# LoRa_test.net
KiCad netlist of a schematic drawn in EAGLE
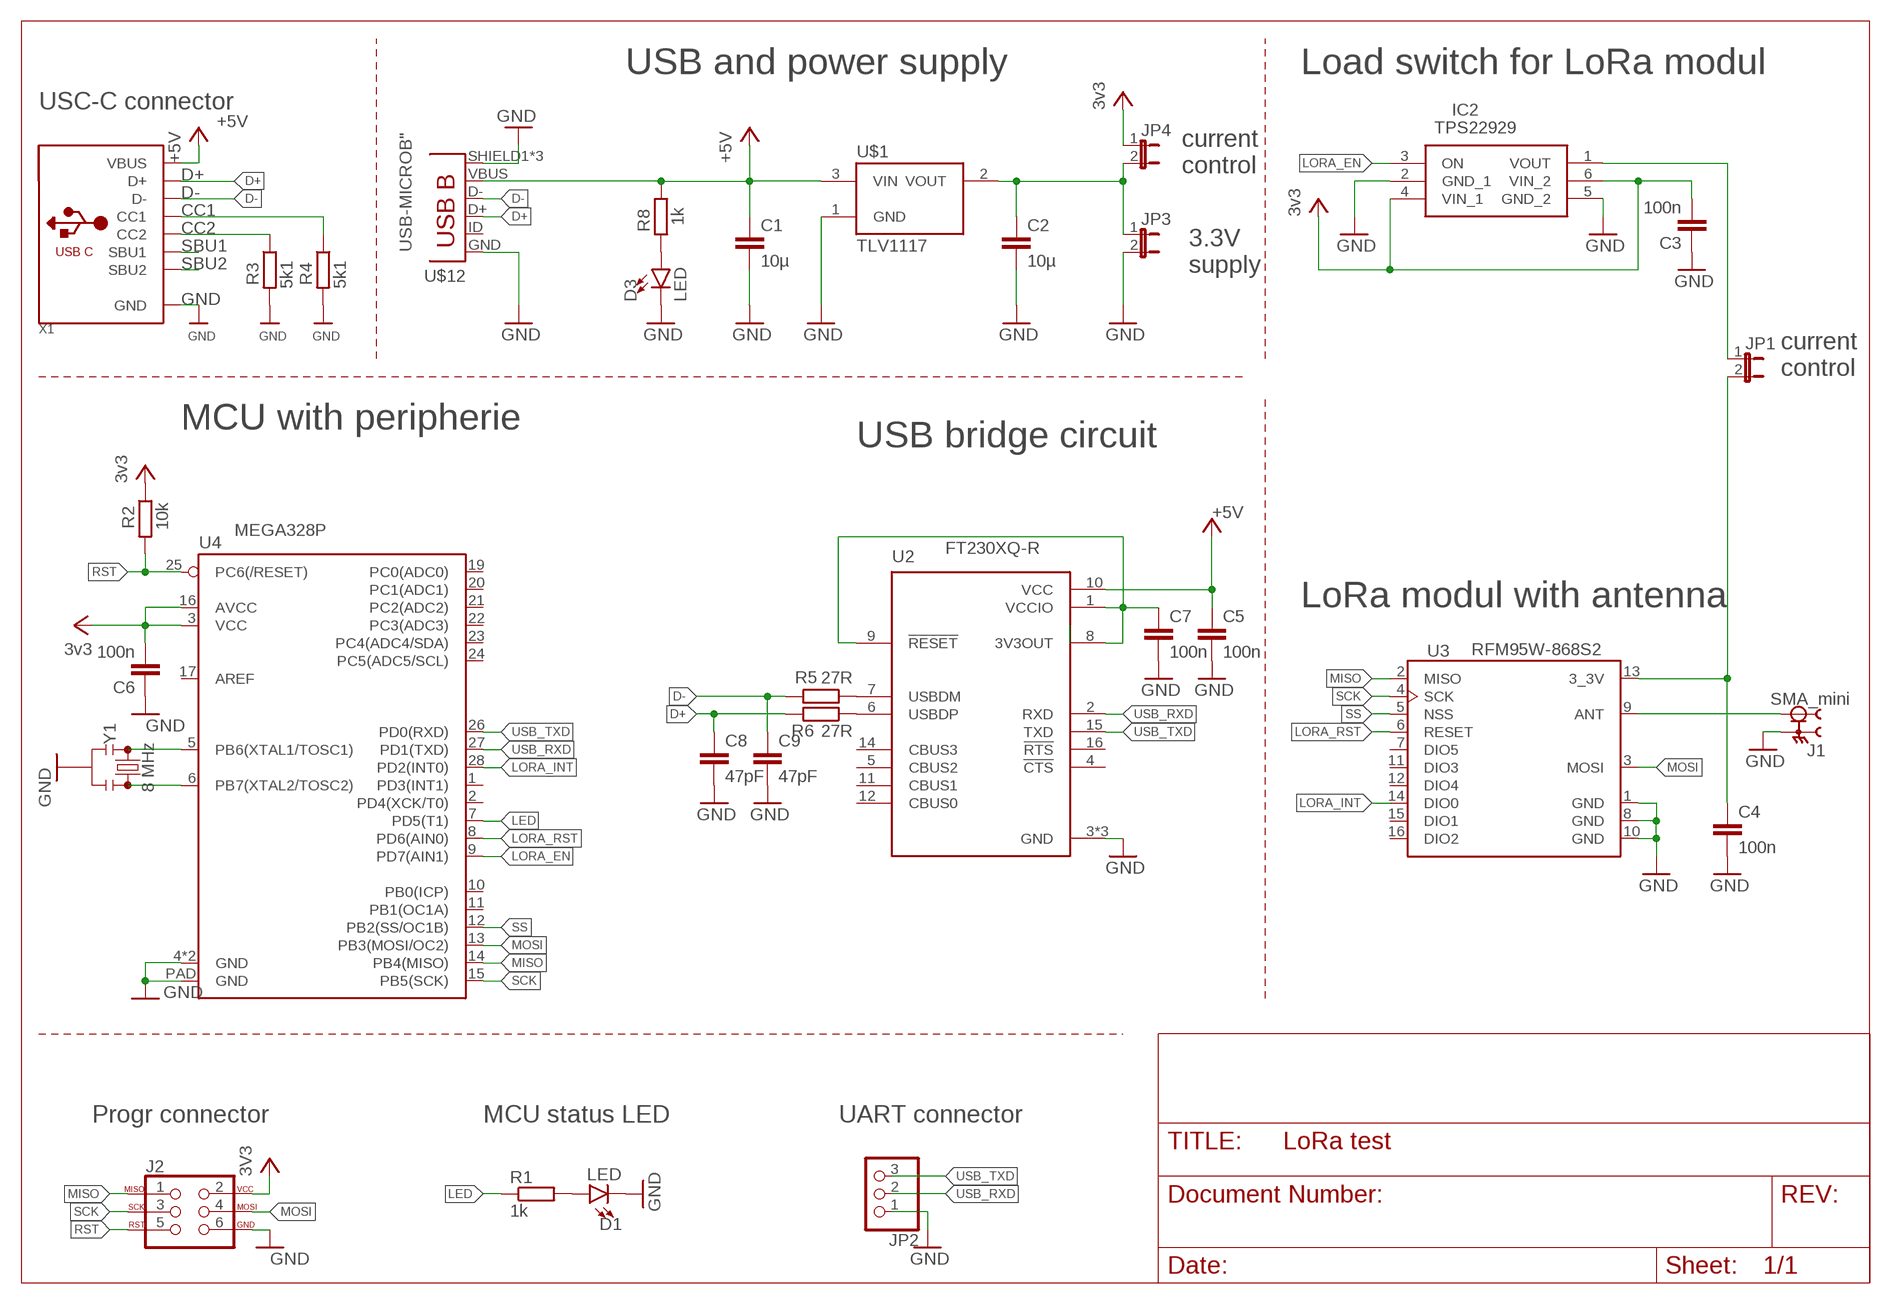
[diagram p0: schematic, sheet 1]

(export (version "E")
  (design (tool "Eeschema 10.0.6"))
  (components
    (comp (ref "C1")
      (value "10µ")
      (footprint "eagle-import:C1206K")
      (libsource (lib "eagle-import") (part "rcl_334_C-EUC1206K"))
    )
    (comp (ref "C2")
      (value "10µ")
      (footprint "eagle-import:C1206K")
      (libsource (lib "eagle-import") (part "rcl_334_C-EUC1206K"))
    )
    (comp (ref "C3")
      (value "100n")
      (footprint "eagle-import:C0603")
      (libsource (lib "eagle-import") (part "C-EUC0603"))
    )
    (comp (ref "C4")
      (value "100n")
      (footprint "eagle-import:C0603")
      (libsource (lib "eagle-import") (part "C-EUC0603"))
    )
    (comp (ref "C5")
      (value "100n")
      (footprint "eagle-import:C0603")
      (libsource (lib "eagle-import") (part "C-EUC0603"))
    )
    (comp (ref "C6")
      (value "100n")
      (footprint "eagle-import:C0603")
      (libsource (lib "eagle-import") (part "C-EUC0603"))
    )
    (comp (ref "C7")
      (value "100n")
      (footprint "eagle-import:C0603")
      (libsource (lib "eagle-import") (part "C-EUC0603"))
    )
    (comp (ref "C8")
      (value "47pF")
      (footprint "eagle-import:C0603")
      (libsource (lib "eagle-import") (part "C-EUC0603"))
    )
    (comp (ref "C9")
      (value "47pF")
      (footprint "eagle-import:C0603")
      (libsource (lib "eagle-import") (part "C-EUC0603"))
    )
    (comp (ref "D1")
      (value "LED")
      (footprint "eagle-import:LED-0603")
      (libsource (lib "eagle-import") (part "LED-RED0603-SMART"))
    )
    (comp (ref "D3")
      (value "LED")
      (footprint "eagle-import:LED-0603")
      (libsource (lib "eagle-import") (part "LED-RED0603"))
    )
    (comp (ref "IC2")
      (value "TPS22929")
      (footprint "eagle-import:SOP95P280X145-6N")
      (fields
        (field (name "ARROW_PART_NUMBER") "TPS22929DDBVR")
        (field (name "MOUSER_PART_NUMBER") "595-TPS22929DDBVR")
      )
      (libsource (lib "eagle-import") (part "TPS22929DDBVR"))
    )
    (comp (ref "J1")
      (value "SMA_mini")
      (footprint "eagle-import:LPRS_SMA_CONNECTOR")
      (fields (field (name "MF") "LPRS") (field (name "MP") "SMA CONNECTOR"))
      (libsource (lib "eagle-import") (part "SMA_CONNECTOR"))
    )
    (comp (ref "J2")
      (value "AVR_SPI_PROG_3X2NS")
      (footprint "eagle-import:2X3-NS")
      (libsource (lib "eagle-import") (part "AVR_SPI_PROG_3X2NS"))
    )
    (comp (ref "JP1")
      (value "JP1E")
      (footprint "eagle-import:JP1")
      (libsource (lib "eagle-import") (part "JP1E"))
    )
    (comp (ref "JP2")
      (value "PINHD-1X3")
      (footprint "eagle-import:1X03")
      (libsource (lib "eagle-import") (part "PINHD-1X3"))
    )
    (comp (ref "JP3")
      (value "JP1E")
      (footprint "eagle-import:JP1")
      (libsource (lib "eagle-import") (part "JP1E"))
    )
    (comp (ref "JP4")
      (value "JP1E")
      (footprint "eagle-import:JP1")
      (libsource (lib "eagle-import") (part "JP1E"))
    )
    (comp (ref "R1")
      (value "1k")
      (footprint "eagle-import:R0603")
      (libsource (lib "eagle-import") (part "R-EU_R0603"))
    )
    (comp (ref "R2")
      (value "10k")
      (footprint "eagle-import:R0603")
      (libsource (lib "eagle-import") (part "R-EU_R0603"))
    )
    (comp (ref "R3")
      (value "5k1")
      (footprint "eagle-import:R0603")
      (libsource (lib "eagle-import") (part "R-EU_R0603"))
    )
    (comp (ref "R4")
      (value "5k1")
      (footprint "eagle-import:R0603")
      (libsource (lib "eagle-import") (part "R-EU_R0603"))
    )
    (comp (ref "R5")
      (value "27R")
      (footprint "eagle-import:R0603")
      (libsource (lib "eagle-import") (part "R-EU_R0603"))
    )
    (comp (ref "R6")
      (value "27R")
      (footprint "eagle-import:R0603")
      (libsource (lib "eagle-import") (part "R-EU_R0603"))
    )
    (comp (ref "R8")
      (value "1k")
      (footprint "eagle-import:R0603")
      (libsource (lib "eagle-import") (part "R-EU_R0603"))
    )
    (comp (ref "U$1")
      (value "TLV1117")
      (footprint "eagle-import:SOT223")
      (libsource (lib "eagle-import") (part "TLV1117"))
    )
    (comp (ref "U$12")
      (value "USB-MICROB\"")
      (footprint "eagle-import:USB-B-MICRO-SMD_V03")
      (libsource (lib "eagle-import") (part "USB-MICROB{dblquote}"))
    )
    (comp (ref "U2")
      (value "FT230XQ-R")
      (footprint "eagle-import:QFN65P400X400X80-17N")
      (fields (field (name "MF") "FTDI,"))
      (libsource (lib "eagle-import") (part "FT230XQ-R"))
    )
    (comp (ref "U3")
      (value "RFM95W-868S2")
      (footprint "eagle-import:XCVR_RFM95W-868S2")
      (fields (field (name "MF") "HOPERF"))
      (libsource (lib "eagle-import") (part "RFM95W-868S2"))
    )
    (comp (ref "U4")
      (value "MEGA328P")
      (footprint "eagle-import:VQFN-28")
      (libsource (lib "eagle-import") (part "ATMEGA328P_VQFNVQFN"))
    )
    (comp (ref "X1")
      (value "USB_C")
      (footprint "eagle-import:USB_C_CUSB31-CFM2AX-01-X")
      (libsource (lib "eagle-import") (part "USB_C"))
    )
    (comp (ref "Y1")
      (value "8 MHz")
      (footprint "eagle-import:RESONATOR-SMD-3.2X1.3")
      (libsource (lib "eagle-import") (part "RESONATORSMD-3.2X1.3"))
    )
  )
  (nets
    (net (code "1") (name "+5V") (class "Default")
      (node (ref "C1") (pin "1") (pinfunction "1_1") (pintype "passive"))
      (node (ref "C5") (pin "1") (pinfunction "1_1") (pintype "passive"))
      (node (ref "R8") (pin "1") (pinfunction "1_1") (pintype "passive"))
      (node (ref "U$1") (pin "3") (pinfunction "VIN_3") (pintype "power_in"))
      (node (ref "U$12") (pin "VBUS") (pinfunction "VBUS_VBUS") (pintype "bidirectional"))
      (node (ref "U2") (pin "10") (pinfunction "VCC_10") (pintype "power_in"))
      (node (ref "X1") (pin "A4B9") (pinfunction "VBUS_A4B9") (pintype "power_in"))
      (node (ref "X1") (pin "B4A9") (pinfunction "VBUS_B4A9") (pintype "power_in"))
    )
    (net (code "2") (name "/CC1") (class "Default")
      (node (ref "R4") (pin "1") (pinfunction "1_1") (pintype "passive"))
      (node (ref "X1") (pin "A5") (pinfunction "CC1_A5") (pintype "bidirectional"))
    )
    (net (code "3") (name "/CC2") (class "Default")
      (node (ref "R3") (pin "1") (pinfunction "1_1") (pintype "passive"))
      (node (ref "X1") (pin "B5") (pinfunction "CC2_B5") (pintype "bidirectional"))
    )
    (net (code "4") (name "/SBU1") (class "Default")
      (node (ref "X1") (pin "A8") (pinfunction "SBU1_A8") (pintype "bidirectional"))
    )
    (net (code "5") (name "/SBU2") (class "Default")
      (node (ref "X1") (pin "B8") (pinfunction "SBU2_B8") (pintype "bidirectional"))
    )
    (net (code "6") (name "3V3") (class "Default")
      (node (ref "C3") (pin "2") (pinfunction "2_2") (pintype "passive"))
      (node (ref "C6") (pin "2") (pinfunction "2_2") (pintype "passive"))
      (node (ref "IC2") (pin "4") (pinfunction "VIN_1_4") (pintype "bidirectional"))
      (node (ref "IC2") (pin "6") (pinfunction "VIN_2_6") (pintype "bidirectional"))
      (node (ref "J2") (pin "2") (pinfunction "2_2") (pintype "passive"))
      (node (ref "JP4") (pin "1") (pinfunction "1_1") (pintype "passive"))
      (node (ref "R2") (pin "1") (pinfunction "1_1") (pintype "passive"))
      (node (ref "U4") (pin "16") (pinfunction "AVCC_16") (pintype "bidirectional"))
      (node (ref "U4") (pin "3") (pinfunction "VCC_3") (pintype "bidirectional"))
    )
    (net (code "7") (name "D+") (class "Default")
      (node (ref "C8") (pin "1") (pinfunction "1_1") (pintype "passive"))
      (node (ref "R6") (pin "2") (pinfunction "2_2") (pintype "passive"))
      (node (ref "U$12") (pin "D+") (pinfunction "D+_D+") (pintype "bidirectional"))
      (node (ref "X1") (pin "A6") (pinfunction "D+_A6") (pintype "bidirectional"))
      (node (ref "X1") (pin "B6") (pinfunction "D+_B6") (pintype "bidirectional"))
    )
    (net (code "8") (name "D-") (class "Default")
      (node (ref "C9") (pin "1") (pinfunction "1_1") (pintype "passive"))
      (node (ref "R5") (pin "2") (pinfunction "2_2") (pintype "passive"))
      (node (ref "U$12") (pin "D-") (pinfunction "D-_D-") (pintype "bidirectional"))
      (node (ref "X1") (pin "A7") (pinfunction "D-_A7") (pintype "bidirectional"))
      (node (ref "X1") (pin "B7") (pinfunction "D-_B7") (pintype "bidirectional"))
    )
    (net (code "9") (name "GND") (class "Default")
      (node (ref "C1") (pin "2") (pinfunction "2_2") (pintype "passive"))
      (node (ref "C2") (pin "2") (pinfunction "2_2") (pintype "passive"))
      (node (ref "C3") (pin "1") (pinfunction "1_1") (pintype "passive"))
      (node (ref "C4") (pin "2") (pinfunction "2_2") (pintype "passive"))
      (node (ref "C5") (pin "2") (pinfunction "2_2") (pintype "passive"))
      (node (ref "C6") (pin "1") (pinfunction "1_1") (pintype "passive"))
      (node (ref "C7") (pin "2") (pinfunction "2_2") (pintype "passive"))
      (node (ref "C8") (pin "2") (pinfunction "2_2") (pintype "passive"))
      (node (ref "C9") (pin "2") (pinfunction "2_2") (pintype "passive"))
      (node (ref "D1") (pin "C") (pinfunction "C_C") (pintype "passive"))
      (node (ref "D3") (pin "C") (pinfunction "C_C") (pintype "passive"))
      (node (ref "IC2") (pin "2") (pinfunction "GND_1_2") (pintype "bidirectional"))
      (node (ref "IC2") (pin "5") (pinfunction "GND_2_5") (pintype "bidirectional"))
      (node (ref "J1") (pin "G1") (pinfunction "2_G1") (pintype "passive"))
      (node (ref "J1") (pin "G2") (pinfunction "2_G2") (pintype "passive"))
      (node (ref "J1") (pin "G3") (pinfunction "2_G3") (pintype "passive"))
      (node (ref "J1") (pin "G4") (pinfunction "2_G4") (pintype "passive"))
      (node (ref "J2") (pin "6") (pinfunction "6_6") (pintype "passive"))
      (node (ref "JP2") (pin "1") (pinfunction "1_1") (pintype "passive"))
      (node (ref "JP3") (pin "2") (pinfunction "2_2") (pintype "passive"))
      (node (ref "R3") (pin "2") (pinfunction "2_2") (pintype "passive"))
      (node (ref "R4") (pin "2") (pinfunction "2_2") (pintype "passive"))
      (node (ref "U$1") (pin "1") (pinfunction "GND_1") (pintype "power_in"))
      (node (ref "U$12") (pin "GND") (pinfunction "GND_GND") (pintype "bidirectional"))
      (node (ref "U$12") (pin "SHIELD1") (pinfunction "SHIELD_SHIELD1") (pintype "bidirectional"))
      (node (ref "U$12") (pin "SHIELD2") (pinfunction "SHIELD_SHIELD2") (pintype "bidirectional"))
      (node (ref "U$12") (pin "SHIELD3") (pinfunction "SHIELD_SHIELD3") (pintype "bidirectional"))
      (node (ref "U2") (pin "13") (pinfunction "GND_13") (pintype "power_in"))
      (node (ref "U2") (pin "17") (pinfunction "GND_17") (pintype "power_in"))
      (node (ref "U2") (pin "3") (pinfunction "GND_3") (pintype "power_in"))
      (node (ref "U3") (pin "1") (pinfunction "GND_1") (pintype "power_in"))
      (node (ref "U3") (pin "10") (pinfunction "GND_10") (pintype "power_in"))
      (node (ref "U3") (pin "8") (pinfunction "GND_8") (pintype "power_in"))
      (node (ref "U4") (pin "18") (pinfunction "GND_18") (pintype "bidirectional"))
      (node (ref "U4") (pin "4") (pinfunction "GND_4") (pintype "bidirectional"))
      (node (ref "U4") (pin "PAD") (pinfunction "GND_PAD") (pintype "bidirectional"))
      (node (ref "X1") (pin "A1B12") (pinfunction "GND_A1B12") (pintype "power_in"))
      (node (ref "X1") (pin "B1A12") (pinfunction "GND_B1A12") (pintype "power_in"))
      (node (ref "Y1") (pin "2") (pinfunction "2_2") (pintype "passive"))
    )
    (net (code "10") (name "LED") (class "Default")
      (node (ref "R1") (pin "1") (pinfunction "1_1") (pintype "passive"))
      (node (ref "U4") (pin "7") (pinfunction "PD5(T1)_7") (pintype "bidirectional"))
    )
    (net (code "11") (name "LORA_EN") (class "Default")
      (node (ref "IC2") (pin "3") (pinfunction "ON_3") (pintype "bidirectional"))
      (node (ref "U4") (pin "9") (pinfunction "PD7(AIN1)_9") (pintype "bidirectional"))
    )
    (net (code "12") (name "LORA_INT") (class "Default")
      (node (ref "U3") (pin "14") (pinfunction "DIO0_14") (pintype "bidirectional"))
      (node (ref "U4") (pin "28") (pinfunction "PD2(INT0)_28") (pintype "bidirectional"))
    )
    (net (code "13") (name "LORA_RST") (class "Default")
      (node (ref "U3") (pin "6") (pinfunction "RESET_6") (pintype "bidirectional"))
      (node (ref "U4") (pin "8") (pinfunction "PD6(AIN0)_8") (pintype "bidirectional"))
    )
    (net (code "14") (name "MISO") (class "Default")
      (node (ref "J2") (pin "1") (pinfunction "1_1") (pintype "passive"))
      (node (ref "U3") (pin "2") (pinfunction "MISO_2") (pintype "input"))
      (node (ref "U4") (pin "14") (pinfunction "PB4(MISO)_14") (pintype "bidirectional"))
    )
    (net (code "15") (name "MOSI") (class "Default")
      (node (ref "J2") (pin "4") (pinfunction "4_4") (pintype "passive"))
      (node (ref "U3") (pin "3") (pinfunction "MOSI_3") (pintype "output"))
      (node (ref "U4") (pin "13") (pinfunction "PB3(MOSI/OC2)_13") (pintype "bidirectional"))
    )
    (net (code "16") (name "Net-(D1-PadA)") (class "Default")
      (node (ref "D1") (pin "A") (pinfunction "A_A") (pintype "passive"))
      (node (ref "R1") (pin "2") (pinfunction "2_2") (pintype "passive"))
    )
    (net (code "17") (name "Net-(D3-PadA)") (class "Default")
      (node (ref "D3") (pin "A") (pinfunction "A_A") (pintype "passive"))
      (node (ref "R8") (pin "2") (pinfunction "2_2") (pintype "passive"))
    )
    (net (code "18") (name "Net-(IC2-VOUT)") (class "Default")
      (node (ref "IC2") (pin "1") (pinfunction "VOUT_1") (pintype "bidirectional"))
      (node (ref "JP1") (pin "1") (pinfunction "1_1") (pintype "passive"))
    )
    (net (code "19") (name "Net-(U$1-VOUT)") (class "Default")
      (node (ref "C2") (pin "1") (pinfunction "1_1") (pintype "passive"))
      (node (ref "JP3") (pin "1") (pinfunction "1_1") (pintype "passive"))
      (node (ref "JP4") (pin "2") (pinfunction "2_2") (pintype "passive"))
      (node (ref "U$1") (pin "2") (pinfunction "VOUT_2") (pintype "power_in"))
      (node (ref "U$1") (pin "4") (pinfunction "VOUT2_4") (pintype "power_in"))
    )
    (net (code "20") (name "Net-(U2-3V3OUT)") (class "Default")
      (node (ref "C7") (pin "1") (pinfunction "1_1") (pintype "passive"))
      (node (ref "U2") (pin "1") (pinfunction "VCCIO_1") (pintype "power_in"))
      (node (ref "U2") (pin "8") (pinfunction "3V3OUT_8") (pintype "output"))
      (node (ref "U2") (pin "9") (pinfunction "~{RESET}_9") (pintype "input"))
    )
    (net (code "21") (name "Net-(U2-USBDM)") (class "Default")
      (node (ref "R5") (pin "1") (pinfunction "1_1") (pintype "passive"))
      (node (ref "U2") (pin "7") (pinfunction "USBDM_7") (pintype "input"))
    )
    (net (code "22") (name "Net-(U2-USBDP)") (class "Default")
      (node (ref "R6") (pin "1") (pinfunction "1_1") (pintype "passive"))
      (node (ref "U2") (pin "6") (pinfunction "USBDP_6") (pintype "input"))
    )
    (net (code "23") (name "Net-(U3-3_3V)") (class "Default")
      (node (ref "C4") (pin "1") (pinfunction "1_1") (pintype "passive"))
      (node (ref "JP1") (pin "2") (pinfunction "2_2") (pintype "passive"))
      (node (ref "U3") (pin "13") (pinfunction "3_3V_13") (pintype "power_in"))
    )
    (net (code "24") (name "Net-(U3-ANT)") (class "Default")
      (node (ref "J1") (pin "1") (pinfunction "1_1") (pintype "passive"))
      (node (ref "U3") (pin "9") (pinfunction "ANT_9") (pintype "passive"))
    )
    (net (code "25") (name "Net-(U4-PB6(XTAL1{slash}TOSC1))") (class "Default")
      (node (ref "U4") (pin "5") (pinfunction "PB6(XTAL1/TOSC1)_5") (pintype "bidirectional"))
      (node (ref "Y1") (pin "1") (pinfunction "1_1") (pintype "passive"))
    )
    (net (code "26") (name "Net-(U4-PB7(XTAL2{slash}TOSC2))") (class "Default")
      (node (ref "U4") (pin "6") (pinfunction "PB7(XTAL2/TOSC2)_6") (pintype "bidirectional"))
      (node (ref "Y1") (pin "3") (pinfunction "3_3") (pintype "passive"))
    )
    (net (code "27") (name "RST") (class "Default")
      (node (ref "J2") (pin "5") (pinfunction "5_5") (pintype "passive"))
      (node (ref "R2") (pin "2") (pinfunction "2_2") (pintype "passive"))
      (node (ref "U4") (pin "25") (pinfunction "PC6(/RESET)_25") (pintype "bidirectional"))
    )
    (net (code "28") (name "SCK") (class "Default")
      (node (ref "J2") (pin "3") (pinfunction "3_3") (pintype "passive"))
      (node (ref "U3") (pin "4") (pinfunction "SCK_4") (pintype "input"))
      (node (ref "U4") (pin "15") (pinfunction "PB5(SCK)_15") (pintype "bidirectional"))
    )
    (net (code "29") (name "SS") (class "Default")
      (node (ref "U3") (pin "5") (pinfunction "NSS_5") (pintype "input"))
      (node (ref "U4") (pin "12") (pinfunction "PB2(SS/OC1B)_12") (pintype "bidirectional"))
    )
    (net (code "30") (name "USB_RXD") (class "Default")
      (node (ref "JP2") (pin "2") (pinfunction "2_2") (pintype "passive"))
      (node (ref "U2") (pin "2") (pinfunction "RXD_2") (pintype "input"))
      (node (ref "U4") (pin "27") (pinfunction "PD1(TXD)_27") (pintype "bidirectional"))
    )
    (net (code "31") (name "USB_TXD") (class "Default")
      (node (ref "JP2") (pin "3") (pinfunction "3_3") (pintype "passive"))
      (node (ref "U2") (pin "15") (pinfunction "TXD_15") (pintype "output"))
      (node (ref "U4") (pin "26") (pinfunction "PD0(RXD)_26") (pintype "bidirectional"))
    )
    (net (code "32") (name "unconnected-(U$12-USBID-PadID)") (class "Default")
      (node (ref "U$12") (pin "ID") (pinfunction "USBID_ID") (pintype "bidirectional"))
    )
    (net (code "33") (name "unconnected-(U2-CBUS0-Pad12)") (class "Default")
      (node (ref "U2") (pin "12") (pinfunction "CBUS0_12") (pintype "bidirectional"))
    )
    (net (code "34") (name "unconnected-(U2-CBUS1-Pad11)") (class "Default")
      (node (ref "U2") (pin "11") (pinfunction "CBUS1_11") (pintype "bidirectional"))
    )
    (net (code "35") (name "unconnected-(U2-CBUS2-Pad5)") (class "Default")
      (node (ref "U2") (pin "5") (pinfunction "CBUS2_5") (pintype "bidirectional"))
    )
    (net (code "36") (name "unconnected-(U2-CBUS3-Pad14)") (class "Default")
      (node (ref "U2") (pin "14") (pinfunction "CBUS3_14") (pintype "bidirectional"))
    )
    (net (code "37") (name "unconnected-(U2-~{CTS}-Pad4)") (class "Default")
      (node (ref "U2") (pin "4") (pinfunction "~{CTS}_4") (pintype "input"))
    )
    (net (code "38") (name "unconnected-(U2-~{RTS}-Pad16)") (class "Default")
      (node (ref "U2") (pin "16") (pinfunction "~{RTS}_16") (pintype "output"))
    )
    (net (code "39") (name "unconnected-(U3-DIO1-Pad15)") (class "Default")
      (node (ref "U3") (pin "15") (pinfunction "DIO1_15") (pintype "bidirectional"))
    )
    (net (code "40") (name "unconnected-(U3-DIO2-Pad16)") (class "Default")
      (node (ref "U3") (pin "16") (pinfunction "DIO2_16") (pintype "bidirectional"))
    )
    (net (code "41") (name "unconnected-(U3-DIO3-Pad11)") (class "Default")
      (node (ref "U3") (pin "11") (pinfunction "DIO3_11") (pintype "bidirectional"))
    )
    (net (code "42") (name "unconnected-(U3-DIO4-Pad12)") (class "Default")
      (node (ref "U3") (pin "12") (pinfunction "DIO4_12") (pintype "bidirectional"))
    )
    (net (code "43") (name "unconnected-(U3-DIO5-Pad7)") (class "Default")
      (node (ref "U3") (pin "7") (pinfunction "DIO5_7") (pintype "bidirectional"))
    )
    (net (code "44") (name "unconnected-(U4-AREF-Pad17)") (class "Default")
      (node (ref "U4") (pin "17") (pinfunction "AREF_17") (pintype "bidirectional"))
    )
    (net (code "45") (name "unconnected-(U4-PB0(ICP)-Pad10)") (class "Default")
      (node (ref "U4") (pin "10") (pinfunction "PB0(ICP)_10") (pintype "bidirectional"))
    )
    (net (code "46") (name "unconnected-(U4-PB1(OC1A)-Pad11)") (class "Default")
      (node (ref "U4") (pin "11") (pinfunction "PB1(OC1A)_11") (pintype "bidirectional"))
    )
    (net (code "47") (name "unconnected-(U4-PC0(ADC0)-Pad19)") (class "Default")
      (node (ref "U4") (pin "19") (pinfunction "PC0(ADC0)_19") (pintype "bidirectional"))
    )
    (net (code "48") (name "unconnected-(U4-PC1(ADC1)-Pad20)") (class "Default")
      (node (ref "U4") (pin "20") (pinfunction "PC1(ADC1)_20") (pintype "bidirectional"))
    )
    (net (code "49") (name "unconnected-(U4-PC2(ADC2)-Pad21)") (class "Default")
      (node (ref "U4") (pin "21") (pinfunction "PC2(ADC2)_21") (pintype "bidirectional"))
    )
    (net (code "50") (name "unconnected-(U4-PC3(ADC3)-Pad22)") (class "Default")
      (node (ref "U4") (pin "22") (pinfunction "PC3(ADC3)_22") (pintype "bidirectional"))
    )
    (net (code "51") (name "unconnected-(U4-PC4(ADC4{slash}SDA)-Pad23)") (class "Default")
      (node (ref "U4") (pin "23") (pinfunction "PC4(ADC4/SDA)_23") (pintype "bidirectional"))
    )
    (net (code "52") (name "unconnected-(U4-PC5(ADC5{slash}SCL)-Pad24)") (class "Default")
      (node (ref "U4") (pin "24") (pinfunction "PC5(ADC5/SCL)_24") (pintype "bidirectional"))
    )
    (net (code "53") (name "unconnected-(U4-PD3(INT1)-Pad1)") (class "Default")
      (node (ref "U4") (pin "1") (pinfunction "PD3(INT1)_1") (pintype "bidirectional"))
    )
    (net (code "54") (name "unconnected-(U4-PD4(XCK{slash}T0)-Pad2)") (class "Default")
      (node (ref "U4") (pin "2") (pinfunction "PD4(XCK/T0)_2") (pintype "bidirectional"))
    )
  )
)
